# OBC_Connectors_PC-104.net
KiCad netlist of a schematic drawn in Altium Designer
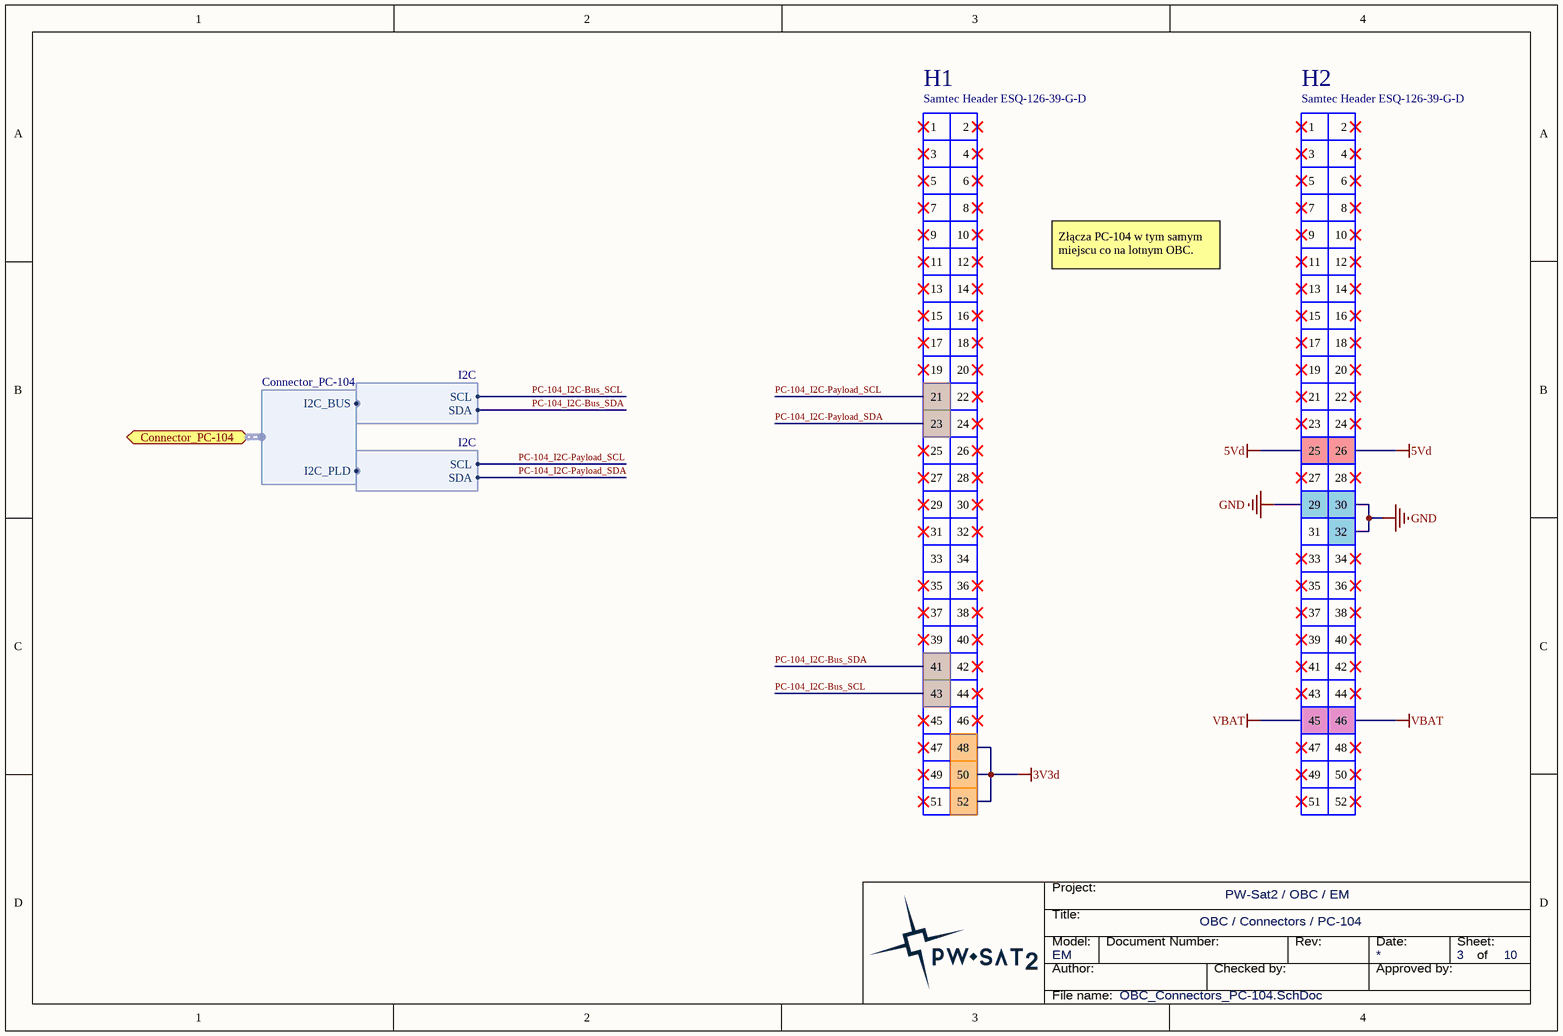
[diagram p0: OBC_Connectors_PC-104.SchDoc]

(export (version "E")
  (design (tool "Eeschema 10.0.6"))
  (components
    (comp (ref "H1")
      (value "Samtec Header ESQ-126-39-G-D")
      (footprint "SAMTEC_ESQ-126-39-G-D")
      (description "Samtec ESQ Series Header , 2.54mm pitch, 2x26pin. PC-104 Stack Connector.")
      (fields (field (name "PARTNO") "ESQ-126-39-G-D") (field (name "MANUFACTURER") "Samtec"))
      (libsource (lib "connectors_printed-circuit-board") (part "Samtec_ESQ-126-xx-x-D"))
    )
    (comp (ref "H2")
      (value "Samtec Header ESQ-126-39-G-D")
      (footprint "SAMTEC_ESQ-126-39-G-D")
      (description "Samtec ESQ Series Header , 2.54mm pitch, 2x26pin. PC-104 Stack Connector.")
      (fields (field (name "PARTNO") "ESQ-126-39-G-D") (field (name "MANUFACTURER") "Samtec"))
      (libsource (lib "connectors_printed-circuit-board") (part "Samtec_ESQ-126-xx-x-D"))
    )
  )
  (nets
    (net (code "2") (name "/PC-104_I2C-Bus_SCL") (class "Default")
      (node (ref "H1") (pin "43") (pinfunction "43_43") (pintype "passive"))
    )
    (net (code "3") (name "/PC-104_I2C-Bus_SDA") (class "Default")
      (node (ref "H1") (pin "41") (pinfunction "41_41") (pintype "passive"))
    )
    (net (code "4") (name "/PC-104_I2C-Payload_SCL") (class "Default")
      (node (ref "H1") (pin "21") (pinfunction "21_21") (pintype "passive"))
    )
    (net (code "5") (name "/PC-104_I2C-Payload_SDA") (class "Default")
      (node (ref "H1") (pin "23") (pinfunction "23_23") (pintype "passive"))
    )
    (net (code "7") (name "3V3d") (class "Default")
      (node (ref "H1") (pin "48") (pinfunction "48_48") (pintype "passive"))
      (node (ref "H1") (pin "50") (pinfunction "50_50") (pintype "passive"))
      (node (ref "H1") (pin "52") (pinfunction "52_52") (pintype "passive"))
    )
    (net (code "8") (name "5Vd") (class "Default")
      (node (ref "H2") (pin "25") (pinfunction "25_25") (pintype "passive"))
      (node (ref "H2") (pin "26") (pinfunction "26_26") (pintype "passive"))
    )
    (net (code "9") (name "GND") (class "Default")
      (node (ref "H2") (pin "29") (pinfunction "29_29") (pintype "passive"))
      (node (ref "H2") (pin "30") (pinfunction "30_30") (pintype "passive"))
      (node (ref "H2") (pin "32") (pinfunction "32_32") (pintype "passive"))
    )
    (net (code "10") (name "VBAT") (class "Default")
      (node (ref "H2") (pin "45") (pinfunction "45_45") (pintype "passive"))
      (node (ref "H2") (pin "46") (pinfunction "46_46") (pintype "passive"))
    )
    (net (code "11") (name "unconnected-(H1-Pad1)") (class "Default")
      (node (ref "H1") (pin "1") (pinfunction "1_1") (pintype "passive+no_connect"))
    )
    (net (code "12") (name "unconnected-(H1-Pad2)") (class "Default")
      (node (ref "H1") (pin "2") (pinfunction "2_2") (pintype "passive+no_connect"))
    )
    (net (code "13") (name "unconnected-(H1-Pad3)") (class "Default")
      (node (ref "H1") (pin "3") (pinfunction "3_3") (pintype "passive+no_connect"))
    )
    (net (code "14") (name "unconnected-(H1-Pad4)") (class "Default")
      (node (ref "H1") (pin "4") (pinfunction "4_4") (pintype "passive+no_connect"))
    )
    (net (code "15") (name "unconnected-(H1-Pad5)") (class "Default")
      (node (ref "H1") (pin "5") (pinfunction "5_5") (pintype "passive+no_connect"))
    )
    (net (code "16") (name "unconnected-(H1-Pad6)") (class "Default")
      (node (ref "H1") (pin "6") (pinfunction "6_6") (pintype "passive+no_connect"))
    )
    (net (code "17") (name "unconnected-(H1-Pad7)") (class "Default")
      (node (ref "H1") (pin "7") (pinfunction "7_7") (pintype "passive+no_connect"))
    )
    (net (code "18") (name "unconnected-(H1-Pad8)") (class "Default")
      (node (ref "H1") (pin "8") (pinfunction "8_8") (pintype "passive+no_connect"))
    )
    (net (code "19") (name "unconnected-(H1-Pad9)") (class "Default")
      (node (ref "H1") (pin "9") (pinfunction "9_9") (pintype "passive+no_connect"))
    )
    (net (code "20") (name "unconnected-(H1-Pad10)") (class "Default")
      (node (ref "H1") (pin "10") (pinfunction "10_10") (pintype "passive+no_connect"))
    )
    (net (code "21") (name "unconnected-(H1-Pad11)") (class "Default")
      (node (ref "H1") (pin "11") (pinfunction "11_11") (pintype "passive+no_connect"))
    )
    (net (code "22") (name "unconnected-(H1-Pad12)") (class "Default")
      (node (ref "H1") (pin "12") (pinfunction "12_12") (pintype "passive+no_connect"))
    )
    (net (code "23") (name "unconnected-(H1-Pad13)") (class "Default")
      (node (ref "H1") (pin "13") (pinfunction "13_13") (pintype "passive+no_connect"))
    )
    (net (code "24") (name "unconnected-(H1-Pad14)") (class "Default")
      (node (ref "H1") (pin "14") (pinfunction "14_14") (pintype "passive+no_connect"))
    )
    (net (code "25") (name "unconnected-(H1-Pad15)") (class "Default")
      (node (ref "H1") (pin "15") (pinfunction "15_15") (pintype "passive+no_connect"))
    )
    (net (code "26") (name "unconnected-(H1-Pad16)") (class "Default")
      (node (ref "H1") (pin "16") (pinfunction "16_16") (pintype "passive+no_connect"))
    )
    (net (code "27") (name "unconnected-(H1-Pad17)") (class "Default")
      (node (ref "H1") (pin "17") (pinfunction "17_17") (pintype "passive+no_connect"))
    )
    (net (code "28") (name "unconnected-(H1-Pad18)") (class "Default")
      (node (ref "H1") (pin "18") (pinfunction "18_18") (pintype "passive+no_connect"))
    )
    (net (code "29") (name "unconnected-(H1-Pad19)") (class "Default")
      (node (ref "H1") (pin "19") (pinfunction "19_19") (pintype "passive+no_connect"))
    )
    (net (code "30") (name "unconnected-(H1-Pad20)") (class "Default")
      (node (ref "H1") (pin "20") (pinfunction "20_20") (pintype "passive+no_connect"))
    )
    (net (code "31") (name "unconnected-(H1-Pad22)") (class "Default")
      (node (ref "H1") (pin "22") (pinfunction "22_22") (pintype "passive+no_connect"))
    )
    (net (code "32") (name "unconnected-(H1-Pad24)") (class "Default")
      (node (ref "H1") (pin "24") (pinfunction "24_24") (pintype "passive+no_connect"))
    )
    (net (code "33") (name "unconnected-(H1-Pad25)") (class "Default")
      (node (ref "H1") (pin "25") (pinfunction "25_25") (pintype "passive+no_connect"))
    )
    (net (code "34") (name "unconnected-(H1-Pad26)") (class "Default")
      (node (ref "H1") (pin "26") (pinfunction "26_26") (pintype "passive+no_connect"))
    )
    (net (code "35") (name "unconnected-(H1-Pad27)") (class "Default")
      (node (ref "H1") (pin "27") (pinfunction "27_27") (pintype "passive+no_connect"))
    )
    (net (code "36") (name "unconnected-(H1-Pad28)") (class "Default")
      (node (ref "H1") (pin "28") (pinfunction "28_28") (pintype "passive+no_connect"))
    )
    (net (code "37") (name "unconnected-(H1-Pad29)") (class "Default")
      (node (ref "H1") (pin "29") (pinfunction "29_29") (pintype "passive+no_connect"))
    )
    (net (code "38") (name "unconnected-(H1-Pad30)") (class "Default")
      (node (ref "H1") (pin "30") (pinfunction "30_30") (pintype "passive+no_connect"))
    )
    (net (code "39") (name "unconnected-(H1-Pad31)") (class "Default")
      (node (ref "H1") (pin "31") (pinfunction "31_31") (pintype "passive+no_connect"))
    )
    (net (code "40") (name "unconnected-(H1-Pad32)") (class "Default")
      (node (ref "H1") (pin "32") (pinfunction "32_32") (pintype "passive+no_connect"))
    )
    (net (code "41") (name "unconnected-(H1-Pad33)") (class "Default")
      (node (ref "H1") (pin "33") (pinfunction "33_33") (pintype "passive"))
    )
    (net (code "42") (name "unconnected-(H1-Pad34)") (class "Default")
      (node (ref "H1") (pin "34") (pinfunction "34_34") (pintype "passive"))
    )
    (net (code "43") (name "unconnected-(H1-Pad35)") (class "Default")
      (node (ref "H1") (pin "35") (pinfunction "35_35") (pintype "passive+no_connect"))
    )
    (net (code "44") (name "unconnected-(H1-Pad36)") (class "Default")
      (node (ref "H1") (pin "36") (pinfunction "36_36") (pintype "passive+no_connect"))
    )
    (net (code "45") (name "unconnected-(H1-Pad37)") (class "Default")
      (node (ref "H1") (pin "37") (pinfunction "37_37") (pintype "passive+no_connect"))
    )
    (net (code "46") (name "unconnected-(H1-Pad38)") (class "Default")
      (node (ref "H1") (pin "38") (pinfunction "38_38") (pintype "passive+no_connect"))
    )
    (net (code "47") (name "unconnected-(H1-Pad39)") (class "Default")
      (node (ref "H1") (pin "39") (pinfunction "39_39") (pintype "passive+no_connect"))
    )
    (net (code "48") (name "unconnected-(H1-Pad40)") (class "Default")
      (node (ref "H1") (pin "40") (pinfunction "40_40") (pintype "passive+no_connect"))
    )
    (net (code "49") (name "unconnected-(H1-Pad42)") (class "Default")
      (node (ref "H1") (pin "42") (pinfunction "42_42") (pintype "passive+no_connect"))
    )
    (net (code "50") (name "unconnected-(H1-Pad44)") (class "Default")
      (node (ref "H1") (pin "44") (pinfunction "44_44") (pintype "passive+no_connect"))
    )
    (net (code "51") (name "unconnected-(H1-Pad45)") (class "Default")
      (node (ref "H1") (pin "45") (pinfunction "45_45") (pintype "passive+no_connect"))
    )
    (net (code "52") (name "unconnected-(H1-Pad46)") (class "Default")
      (node (ref "H1") (pin "46") (pinfunction "46_46") (pintype "passive+no_connect"))
    )
    (net (code "53") (name "unconnected-(H1-Pad47)") (class "Default")
      (node (ref "H1") (pin "47") (pinfunction "47_47") (pintype "passive+no_connect"))
    )
    (net (code "54") (name "unconnected-(H1-Pad49)") (class "Default")
      (node (ref "H1") (pin "49") (pinfunction "49_49") (pintype "passive+no_connect"))
    )
    (net (code "55") (name "unconnected-(H1-Pad51)") (class "Default")
      (node (ref "H1") (pin "51") (pinfunction "51_51") (pintype "passive+no_connect"))
    )
    (net (code "56") (name "unconnected-(H2-Pad1)") (class "Default")
      (node (ref "H2") (pin "1") (pinfunction "1_1") (pintype "passive+no_connect"))
    )
    (net (code "57") (name "unconnected-(H2-Pad2)") (class "Default")
      (node (ref "H2") (pin "2") (pinfunction "2_2") (pintype "passive+no_connect"))
    )
    (net (code "58") (name "unconnected-(H2-Pad3)") (class "Default")
      (node (ref "H2") (pin "3") (pinfunction "3_3") (pintype "passive+no_connect"))
    )
    (net (code "59") (name "unconnected-(H2-Pad4)") (class "Default")
      (node (ref "H2") (pin "4") (pinfunction "4_4") (pintype "passive+no_connect"))
    )
    (net (code "60") (name "unconnected-(H2-Pad5)") (class "Default")
      (node (ref "H2") (pin "5") (pinfunction "5_5") (pintype "passive+no_connect"))
    )
    (net (code "61") (name "unconnected-(H2-Pad6)") (class "Default")
      (node (ref "H2") (pin "6") (pinfunction "6_6") (pintype "passive+no_connect"))
    )
    (net (code "62") (name "unconnected-(H2-Pad7)") (class "Default")
      (node (ref "H2") (pin "7") (pinfunction "7_7") (pintype "passive+no_connect"))
    )
    (net (code "63") (name "unconnected-(H2-Pad8)") (class "Default")
      (node (ref "H2") (pin "8") (pinfunction "8_8") (pintype "passive+no_connect"))
    )
    (net (code "64") (name "unconnected-(H2-Pad9)") (class "Default")
      (node (ref "H2") (pin "9") (pinfunction "9_9") (pintype "passive+no_connect"))
    )
    (net (code "65") (name "unconnected-(H2-Pad10)") (class "Default")
      (node (ref "H2") (pin "10") (pinfunction "10_10") (pintype "passive+no_connect"))
    )
    (net (code "66") (name "unconnected-(H2-Pad11)") (class "Default")
      (node (ref "H2") (pin "11") (pinfunction "11_11") (pintype "passive+no_connect"))
    )
    (net (code "67") (name "unconnected-(H2-Pad12)") (class "Default")
      (node (ref "H2") (pin "12") (pinfunction "12_12") (pintype "passive+no_connect"))
    )
    (net (code "68") (name "unconnected-(H2-Pad13)") (class "Default")
      (node (ref "H2") (pin "13") (pinfunction "13_13") (pintype "passive+no_connect"))
    )
    (net (code "69") (name "unconnected-(H2-Pad14)") (class "Default")
      (node (ref "H2") (pin "14") (pinfunction "14_14") (pintype "passive+no_connect"))
    )
    (net (code "70") (name "unconnected-(H2-Pad15)") (class "Default")
      (node (ref "H2") (pin "15") (pinfunction "15_15") (pintype "passive+no_connect"))
    )
    (net (code "71") (name "unconnected-(H2-Pad16)") (class "Default")
      (node (ref "H2") (pin "16") (pinfunction "16_16") (pintype "passive+no_connect"))
    )
    (net (code "72") (name "unconnected-(H2-Pad17)") (class "Default")
      (node (ref "H2") (pin "17") (pinfunction "17_17") (pintype "passive+no_connect"))
    )
    (net (code "73") (name "unconnected-(H2-Pad18)") (class "Default")
      (node (ref "H2") (pin "18") (pinfunction "18_18") (pintype "passive+no_connect"))
    )
    (net (code "74") (name "unconnected-(H2-Pad19)") (class "Default")
      (node (ref "H2") (pin "19") (pinfunction "19_19") (pintype "passive+no_connect"))
    )
    (net (code "75") (name "unconnected-(H2-Pad20)") (class "Default")
      (node (ref "H2") (pin "20") (pinfunction "20_20") (pintype "passive+no_connect"))
    )
    (net (code "76") (name "unconnected-(H2-Pad21)") (class "Default")
      (node (ref "H2") (pin "21") (pinfunction "21_21") (pintype "passive+no_connect"))
    )
    (net (code "77") (name "unconnected-(H2-Pad22)") (class "Default")
      (node (ref "H2") (pin "22") (pinfunction "22_22") (pintype "passive+no_connect"))
    )
    (net (code "78") (name "unconnected-(H2-Pad23)") (class "Default")
      (node (ref "H2") (pin "23") (pinfunction "23_23") (pintype "passive+no_connect"))
    )
    (net (code "79") (name "unconnected-(H2-Pad24)") (class "Default")
      (node (ref "H2") (pin "24") (pinfunction "24_24") (pintype "passive+no_connect"))
    )
    (net (code "80") (name "unconnected-(H2-Pad27)") (class "Default")
      (node (ref "H2") (pin "27") (pinfunction "27_27") (pintype "passive+no_connect"))
    )
    (net (code "81") (name "unconnected-(H2-Pad28)") (class "Default")
      (node (ref "H2") (pin "28") (pinfunction "28_28") (pintype "passive+no_connect"))
    )
    (net (code "82") (name "unconnected-(H2-Pad31)") (class "Default")
      (node (ref "H2") (pin "31") (pinfunction "31_31") (pintype "passive"))
    )
    (net (code "83") (name "unconnected-(H2-Pad33)") (class "Default")
      (node (ref "H2") (pin "33") (pinfunction "33_33") (pintype "passive+no_connect"))
    )
    (net (code "84") (name "unconnected-(H2-Pad34)") (class "Default")
      (node (ref "H2") (pin "34") (pinfunction "34_34") (pintype "passive+no_connect"))
    )
    (net (code "85") (name "unconnected-(H2-Pad35)") (class "Default")
      (node (ref "H2") (pin "35") (pinfunction "35_35") (pintype "passive+no_connect"))
    )
    (net (code "86") (name "unconnected-(H2-Pad36)") (class "Default")
      (node (ref "H2") (pin "36") (pinfunction "36_36") (pintype "passive+no_connect"))
    )
    (net (code "87") (name "unconnected-(H2-Pad37)") (class "Default")
      (node (ref "H2") (pin "37") (pinfunction "37_37") (pintype "passive+no_connect"))
    )
    (net (code "88") (name "unconnected-(H2-Pad38)") (class "Default")
      (node (ref "H2") (pin "38") (pinfunction "38_38") (pintype "passive+no_connect"))
    )
    (net (code "89") (name "unconnected-(H2-Pad39)") (class "Default")
      (node (ref "H2") (pin "39") (pinfunction "39_39") (pintype "passive+no_connect"))
    )
    (net (code "90") (name "unconnected-(H2-Pad40)") (class "Default")
      (node (ref "H2") (pin "40") (pinfunction "40_40") (pintype "passive+no_connect"))
    )
    (net (code "91") (name "unconnected-(H2-Pad41)") (class "Default")
      (node (ref "H2") (pin "41") (pinfunction "41_41") (pintype "passive+no_connect"))
    )
    (net (code "92") (name "unconnected-(H2-Pad42)") (class "Default")
      (node (ref "H2") (pin "42") (pinfunction "42_42") (pintype "passive+no_connect"))
    )
    (net (code "93") (name "unconnected-(H2-Pad43)") (class "Default")
      (node (ref "H2") (pin "43") (pinfunction "43_43") (pintype "passive+no_connect"))
    )
    (net (code "94") (name "unconnected-(H2-Pad44)") (class "Default")
      (node (ref "H2") (pin "44") (pinfunction "44_44") (pintype "passive+no_connect"))
    )
    (net (code "95") (name "unconnected-(H2-Pad47)") (class "Default")
      (node (ref "H2") (pin "47") (pinfunction "47_47") (pintype "passive+no_connect"))
    )
    (net (code "96") (name "unconnected-(H2-Pad48)") (class "Default")
      (node (ref "H2") (pin "48") (pinfunction "48_48") (pintype "passive+no_connect"))
    )
    (net (code "97") (name "unconnected-(H2-Pad49)") (class "Default")
      (node (ref "H2") (pin "49") (pinfunction "49_49") (pintype "passive+no_connect"))
    )
    (net (code "98") (name "unconnected-(H2-Pad50)") (class "Default")
      (node (ref "H2") (pin "50") (pinfunction "50_50") (pintype "passive+no_connect"))
    )
    (net (code "99") (name "unconnected-(H2-Pad51)") (class "Default")
      (node (ref "H2") (pin "51") (pinfunction "51_51") (pintype "passive+no_connect"))
    )
    (net (code "100") (name "unconnected-(H2-Pad52)") (class "Default")
      (node (ref "H2") (pin "52") (pinfunction "52_52") (pintype "passive+no_connect"))
    )
  )
)
